# Adafruit_DRV8871.net
KiCad netlist of a schematic drawn in EAGLE
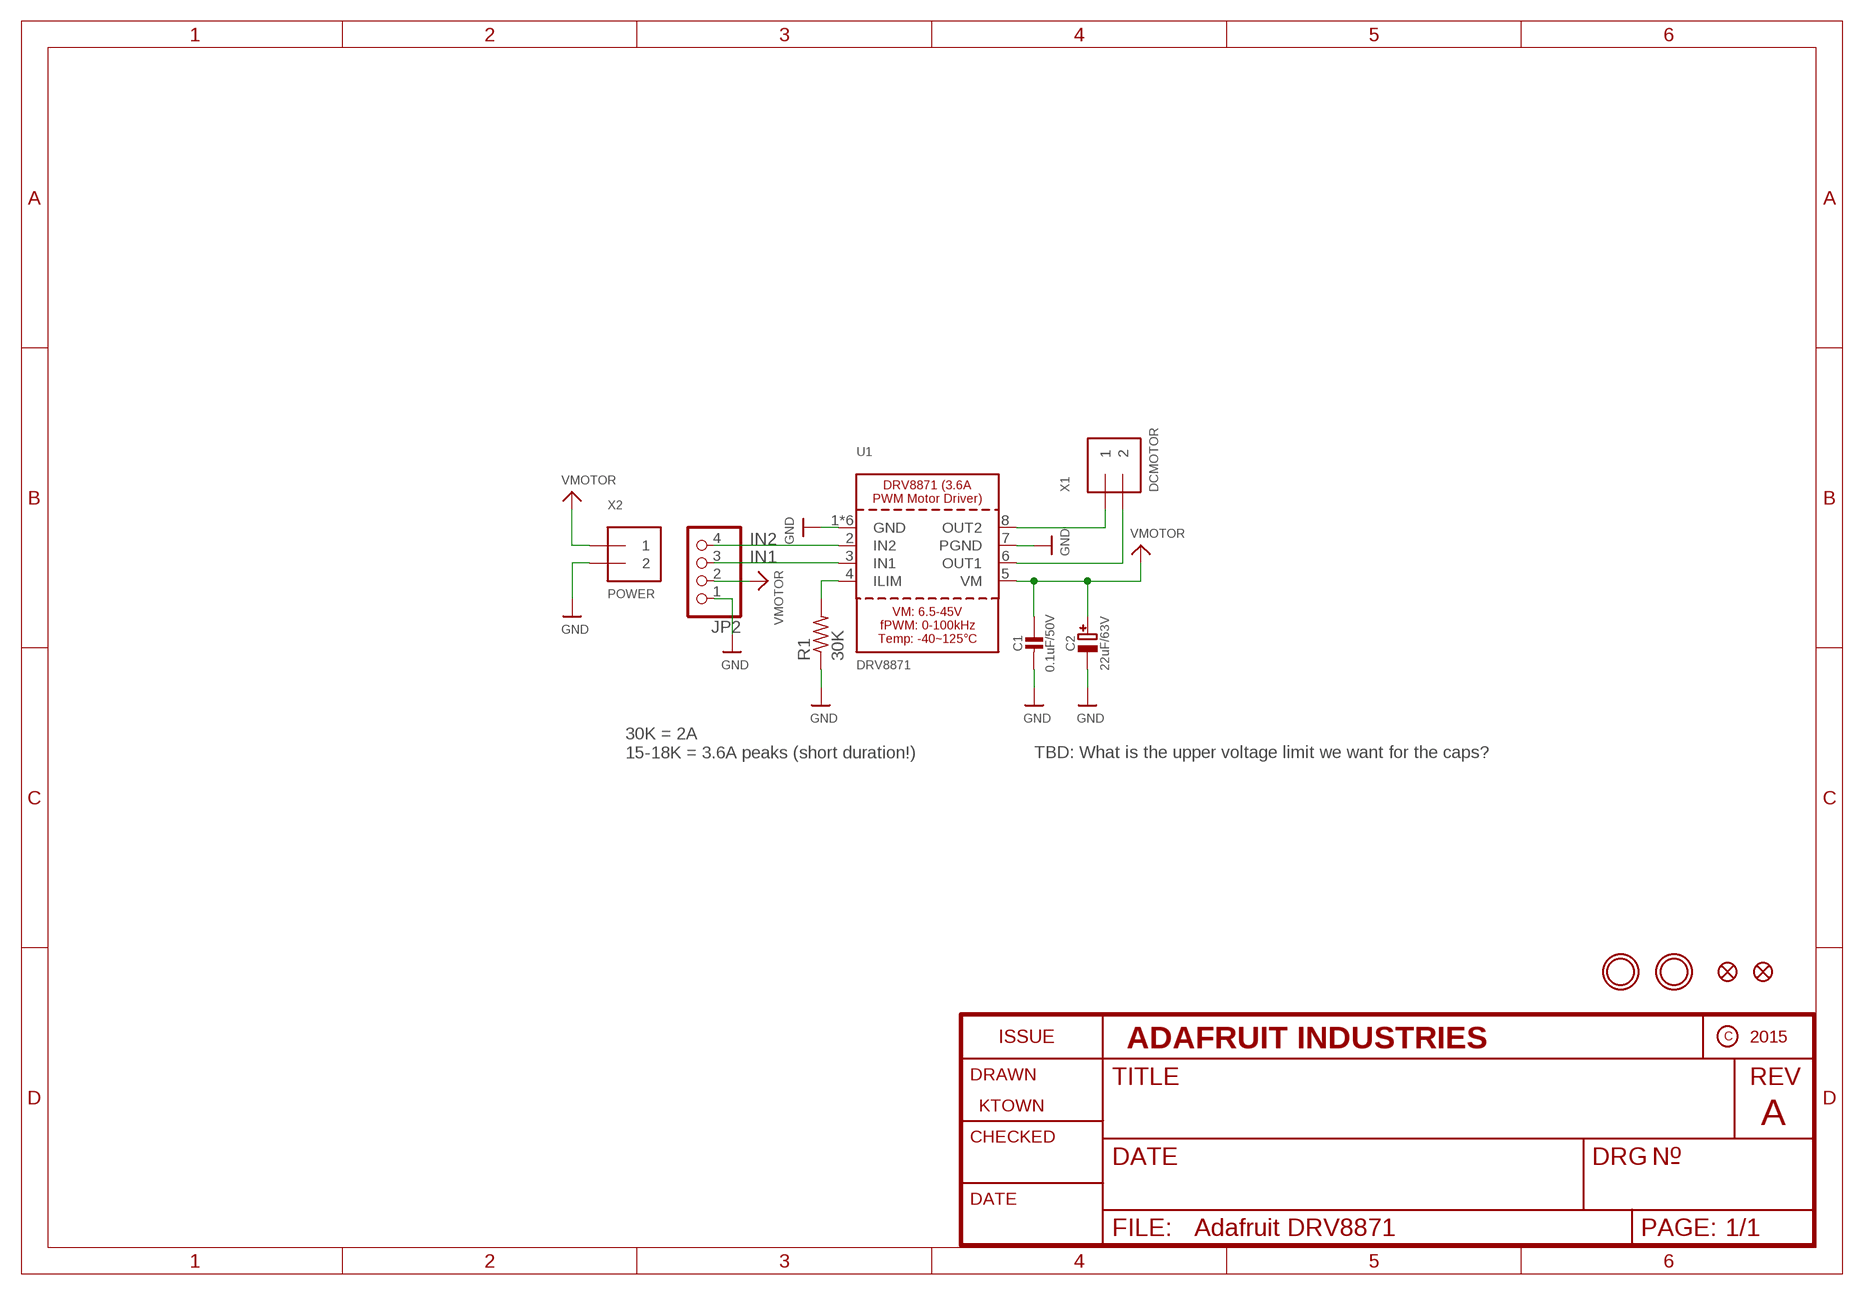
[diagram p0: schematic, sheet 1]

(export (version "E")
  (design (tool "Eeschema 10.0.6"))
  (components
    (comp (ref "C1")
      (value "0.1uF/50V")
      (footprint "eagle-import:0805-NO")
      (libsource (lib "eagle-import") (part "CAP_CERAMIC0805-NOOUTLINE"))
    )
    (comp (ref "C2")
      (value "22uF/63V")
      (footprint "eagle-import:PANASONIC_D")
      (libsource (lib "eagle-import") (part "CAP_ELECTROLYTICPANASONIC_D"))
    )
    (comp (ref "FID1")
      (value "FIDUCIAL\"\"")
      (footprint "eagle-import:FIDUCIAL_1MM")
      (libsource (lib "eagle-import") (part "FIDUCIAL{dblquote}{dblquote}"))
    )
    (comp (ref "FID2")
      (value "FIDUCIAL\"\"")
      (footprint "eagle-import:FIDUCIAL_1MM")
      (libsource (lib "eagle-import") (part "FIDUCIAL{dblquote}{dblquote}"))
    )
    (comp (ref "JP2")
      (value "HEADER-1X476MIL")
      (footprint "eagle-import:1X04_ROUND_76")
      (libsource (lib "eagle-import") (part "HEADER-1X476MIL"))
    )
    (comp (ref "R1")
      (value "30K")
      (footprint "eagle-import:0805-THM")
      (libsource (lib "eagle-import") (part "FLIPFLOP-RES"))
    )
    (comp (ref "U$9")
      (value "MOUNTINGHOLE2.5")
      (footprint "eagle-import:MOUNTINGHOLE_2.5_PLATED")
      (libsource (lib "eagle-import") (part "MOUNTINGHOLE2.5"))
    )
    (comp (ref "U$10")
      (value "MOUNTINGHOLE2.5")
      (footprint "eagle-import:MOUNTINGHOLE_2.5_PLATED")
      (libsource (lib "eagle-import") (part "MOUNTINGHOLE2.5"))
    )
    (comp (ref "U1")
      (value "DRV8871")
      (footprint "eagle-import:HSOP8")
      (libsource (lib "eagle-import") (part "DRV8871"))
    )
    (comp (ref "X1")
      (value "DCMOTOR")
      (footprint "eagle-import:TERMBLOCK_1X2-3.5MM")
      (libsource (lib "eagle-import") (part "TERMBLOCK_1X2"))
    )
    (comp (ref "X2")
      (value "POWER")
      (footprint "eagle-import:TERMBLOCK_1X2-3.5MM")
      (libsource (lib "eagle-import") (part "TERMBLOCK_1X2"))
    )
  )
  (nets
    (net (code "1") (name "/IN1") (class "Default")
      (node (ref "JP2") (pin "3") (pinfunction "3_3") (pintype "passive"))
      (node (ref "U1") (pin "3") (pinfunction "IN1_3") (pintype "input"))
    )
    (net (code "2") (name "/IN2") (class "Default")
      (node (ref "JP2") (pin "4") (pinfunction "4_4") (pintype "passive"))
      (node (ref "U1") (pin "2") (pinfunction "IN2_2") (pintype "input"))
    )
    (net (code "3") (name "GND") (class "Default")
      (node (ref "C1") (pin "2") (pinfunction "2_2") (pintype "passive"))
      (node (ref "C2") (pin "-") (pinfunction "-_-") (pintype "passive"))
      (node (ref "JP2") (pin "1") (pinfunction "1_1") (pintype "passive"))
      (node (ref "R1") (pin "1") (pinfunction "1_1") (pintype "passive"))
      (node (ref "U1") (pin "1") (pinfunction "GND_1") (pintype "power_in"))
      (node (ref "U1") (pin "7") (pinfunction "PGND_7") (pintype "power_in"))
      (node (ref "U1") (pin "GND") (pinfunction "GND_GND") (pintype "power_in"))
      (node (ref "U1") (pin "P$1") (pinfunction "GND_P$1") (pintype "power_in"))
      (node (ref "U1") (pin "P$2") (pinfunction "GND_P$2") (pintype "power_in"))
      (node (ref "U1") (pin "P$3") (pinfunction "GND_P$3") (pintype "power_in"))
      (node (ref "U1") (pin "P$4") (pinfunction "GND_P$4") (pintype "power_in"))
      (node (ref "X2") (pin "2") (pinfunction "2_2") (pintype "passive"))
    )
    (net (code "4") (name "Net-(U1-ILIM)") (class "Default")
      (node (ref "R1") (pin "2") (pinfunction "2_2") (pintype "passive"))
      (node (ref "U1") (pin "4") (pinfunction "ILIM_4") (pintype "input"))
    )
    (net (code "5") (name "Net-(U1-OUT1)") (class "Default")
      (node (ref "U1") (pin "6") (pinfunction "OUT1_6") (pintype "output"))
      (node (ref "X1") (pin "2") (pinfunction "2_2") (pintype "passive"))
    )
    (net (code "6") (name "Net-(U1-OUT2)") (class "Default")
      (node (ref "U1") (pin "8") (pinfunction "OUT2_8") (pintype "output"))
      (node (ref "X1") (pin "1") (pinfunction "1_1") (pintype "passive"))
    )
    (net (code "7") (name "VMOTOR") (class "Default")
      (node (ref "C1") (pin "1") (pinfunction "1_1") (pintype "passive"))
      (node (ref "C2") (pin "+") (pinfunction "+_+") (pintype "passive"))
      (node (ref "JP2") (pin "2") (pinfunction "2_2") (pintype "passive"))
      (node (ref "U1") (pin "5") (pinfunction "VM_5") (pintype "power_in"))
      (node (ref "X2") (pin "1") (pinfunction "1_1") (pintype "passive"))
    )
  )
)
